# ETS_v8-nordic-split.net
KiCad netlist of a schematic drawn in Altium Designer
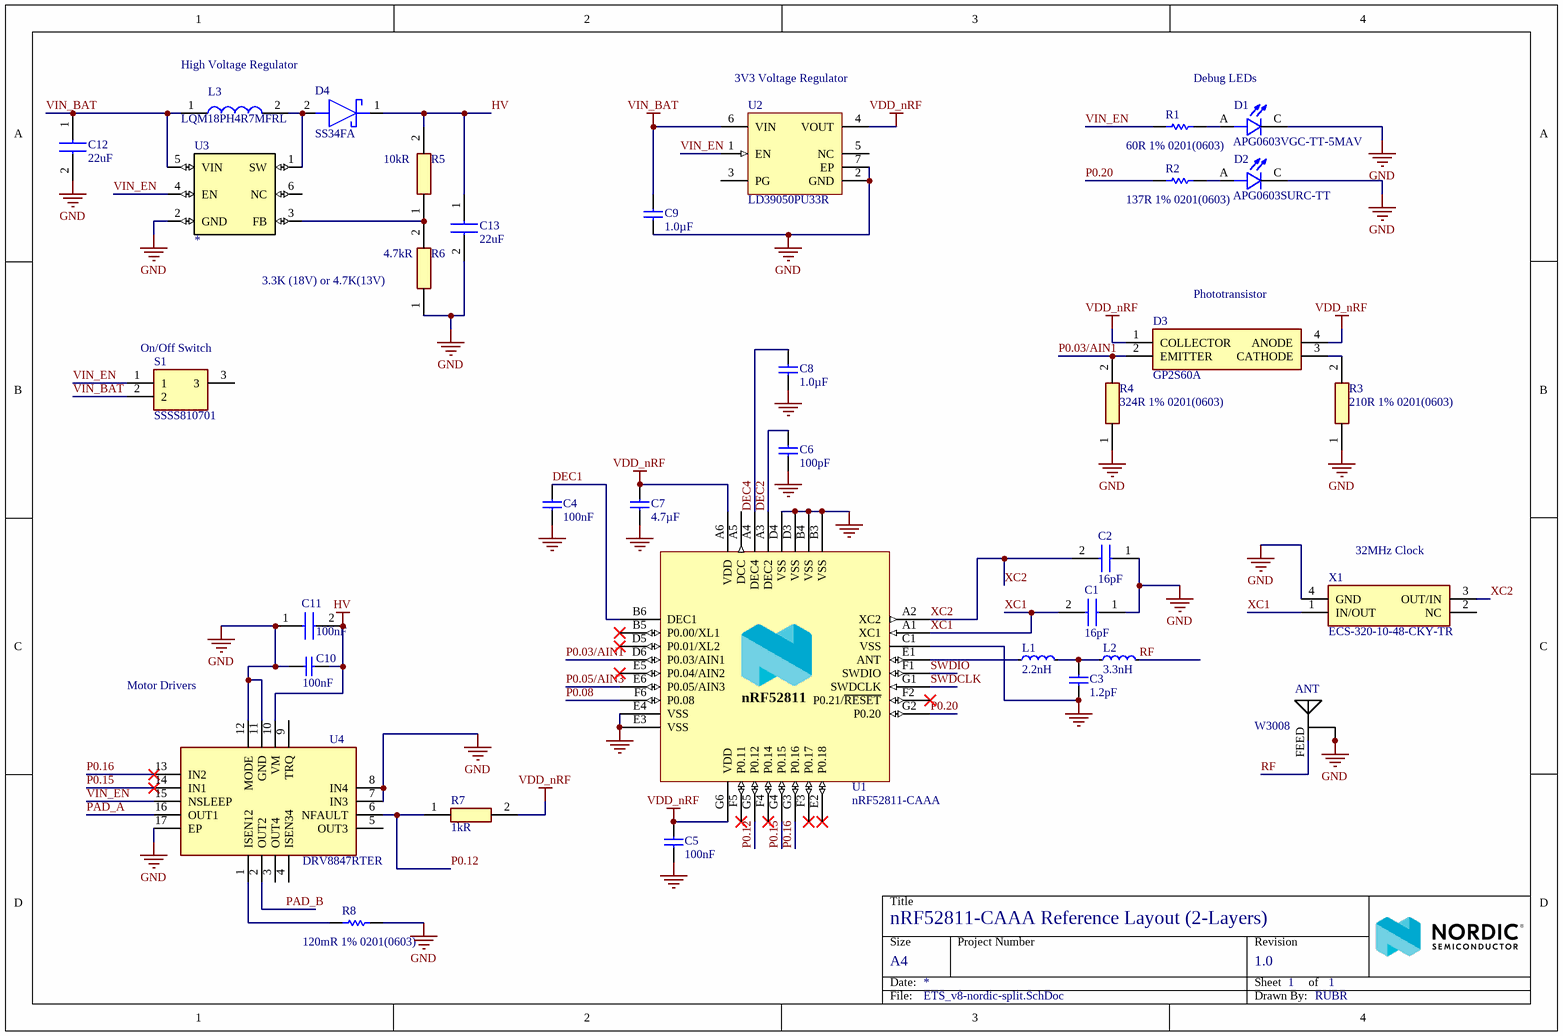
[diagram p0: ETS_v8-nordic-split.SchDoc]

(export (version "E")
  (design (tool "Eeschema 10.0.6"))
  (components
    (comp (ref "ANT")
      (value "W3008")
      (footprint "*ANTENNA_W3008W3008(Primary)")
      (description "2.4GHz Bluetooth Chip RF Antenna 2.4GHz ~ 2.483GHz 1.7dBi Solder Surface Mount")
      (fields (field (name "MF") "PulseLarsen Antennas"))
      (libsource (lib "W3008") (part "W3008"))
    )
    (comp (ref "C1")
      (value "16pF")
      (footprint "SamacSys:CAPC0603X33N")
      (description "Capacitor")
      (fields (field (name "MANUFACTURER_PART_NUMBER") "GRM0335C1H160JA01D"))
      (libsource (lib "*") (part "GRM0335C1H160JA01D"))
    )
    (comp (ref "C2")
      (value "16pF")
      (footprint "SamacSys:CAPC0603X33N")
      (description "Capacitor")
      (fields (field (name "MANUFACTURER_PART_NUMBER") "GRM0335C1H160JA01D"))
      (libsource (lib "*") (part "GRM0335C1H160JA01D"))
    )
    (comp (ref "C3")
      (value "1.2pF")
      (footprint "CAPC0603X03L_C")
      (description "Capacitor, NP0, ±5%")
      (fields (field (name "PART NUMBER") "C0201-1.2p") (field (name "PUBLISHER") "Nordic Semiconductor"))
      (libsource (lib "Nordic Passive DB") (part "CAP"))
    )
    (comp (ref "C4")
      (value "100nF")
      (footprint "CAPC0603X03L_C")
      (description "Capacitor, X5R, ±10%")
      (fields (field (name "PART NUMBER") "C0201-100n") (field (name "PUBLISHER") "Nordic Semiconductor"))
      (libsource (lib "Nordic Passive DB") (part "CAP"))
    )
    (comp (ref "C5")
      (value "100nF")
      (footprint "CAPC0603X03L_C")
      (description "Capacitor, X5R, ±10%")
      (fields (field (name "PART NUMBER") "C0201-100n") (field (name "PUBLISHER") "Nordic Semiconductor"))
      (libsource (lib "Nordic Passive DB") (part "CAP"))
    )
    (comp (ref "C6")
      (value "100pF")
      (footprint "CAPC0603X03L_C")
      (description "Capacitor, NP0, ±2%")
      (fields (field (name "PART NUMBER") "C0201-100p") (field (name "PUBLISHER") "Nordic Semiconductor"))
      (libsource (lib "Nordic Passive DB") (part "CAP"))
    )
    (comp (ref "C7")
      (value "4.7µF")
      (footprint "CAPC1608X06L")
      (description "Capacitor, X5R, ±10%")
      (fields (field (name "PART NUMBER") "C0603-4µ7") (field (name "PUBLISHER") "Nordic Semiconductor"))
      (libsource (lib "Nordic Passive DB") (part "CAP"))
    )
    (comp (ref "C8")
      (value "1.0µF")
      (footprint "CAPC1005X04L")
      (description "Capacitor, X5R, ±5%")
      (fields (field (name "PART NUMBER") "C0402-1µ0") (field (name "PUBLISHER") "Nordic Semiconductor"))
      (libsource (lib "Nordic Passive DB") (part "CAP"))
    )
    (comp (ref "C9")
      (value "1.0µF")
      (footprint "CAPC1005X04L")
      (description "Capacitor, X5R, ±5%")
      (fields (field (name "PART NUMBER") "C0402-1µ0") (field (name "PUBLISHER") "Nordic Semiconductor"))
      (libsource (lib "Nordic Passive DB") (part "CAP"))
    )
    (comp (ref "C10")
      (value "100nF")
      (footprint "CAPC0603X03L_C")
      (description "Capacitor, X5R, ±10%")
      (fields (field (name "PART NUMBER") "C0201-100n") (field (name "PUBLISHER") "Nordic Semiconductor"))
      (libsource (lib "exoNail_v1") (part "C0201-100n"))
    )
    (comp (ref "C11")
      (value "100nF")
      (footprint "CAPC0603X03L_C")
      (description "Capacitor")
      (fields (field (name "MANUFACTURER_PART_NUMBER") "GRM188R61C106KAALD"))
      (libsource (lib "*") (part "GRM188R61C106KAALD"))
    )
    (comp (ref "C12")
      (value "22uF")
      (footprint "CAPC2012X145N")
      (description "Capacitor")
      (fields (field (name "MANUFACTURER_PART_NUMBER") "GRM21BR61E226ME44K"))
      (libsource (lib "MasterLib") (part "GRM21BR61E226ME44K"))
    )
    (comp (ref "C13")
      (value "22uF")
      (footprint "CAPC2012X145N")
      (description "Capacitor")
      (fields (field (name "MANUFACTURER_PART_NUMBER") "GRM21BR61E226ME44K"))
      (libsource (lib "MasterLib") (part "GRM21BR61E226ME44K"))
    )
    (comp (ref "D1")
      (value "APG0603VGC-TT-5MAV")
      (footprint "LED_APG0603SEC-E-TT")
      (description "Green 527nm LED Indication - Discrete 3V 2-SMD, 0201")
      (fields (field (name "MP") "APG0603SEC-E-TT") (field (name "MF") "Kingbright"))
      (libsource (lib "APG0603SEC-E-TT") (part "APG0603SEC-E-TT"))
    )
    (comp (ref "D2")
      (value "APG0603SURC-TT")
      (footprint "LED_APG0603SEC-E-TT")
      (description "Red 631nm LED Indication - Discrete 1.92V 2-SMD, 0201")
      (fields (field (name "MP") "APG0603SEC-E-TT") (field (name "MF") "Kingbright"))
      (libsource (lib "APG0603SEC-E-TT") (part "APG0603SEC-E-TT"))
    )
    (comp (ref "D3")
      (value "GP2S60A")
      (footprint "SamacSys:GP2S60B")
      (description "LED")
      (fields
        (field (name "MOUSER2 PART NUMBER") "852-GP2S60B")
        (field (name "MANUFACTURER_PART_NUMBER") "GP2S60B")
      )
      (libsource (lib "*") (part "GP2S60B"))
    )
    (comp (ref "D4")
      (value "SS34FA")
      (footprint "SamacSys:SODFL3618X143N")
      (description "Schottky Diode")
      (fields (field (name "MOUSER2 PART NUMBER") "512-SS34FA"))
      (libsource (lib "*") (part "SS34FA"))
    )
    (comp (ref "L1")
      (value "2.2nH")
      (footprint "INDC0603X03L_C")
      (description "High frequency chip inductor ±5%")
      (fields (field (name "PART NUMBER") "L0201-2n2") (field (name "PUBLISHER") "Nordic Semiconductor"))
      (libsource (lib "Nordic Passive DB") (part "IND"))
    )
    (comp (ref "L2")
      (value "3.3nH")
      (footprint "INDC0603X03L_C")
      (description "High frequency chip inductor ±5%")
      (fields (field (name "PART NUMBER") "L0201-3n3") (field (name "PUBLISHER") "Nordic Semiconductor"))
      (libsource (lib "Nordic Passive DB") (part "IND"))
    )
    (comp (ref "L3")
      (value "LQM18PH4R7MFRL")
      (footprint "SamacSys:LQW18CA32NJ00D")
      (description "Inductor")
      (fields (field (name "MOUSER2 PART NUMBER") "81-LQM18PH4R7MFRL"))
      (libsource (lib "*") (part "LQM18PH4R7MFRL"))
    )
    (comp (ref "R1")
      (value "60R 1% 0201(0603)")
      (footprint "RESC0201(0603)_L")
      (description "1R 0.05W 1% 0201 (0603 Metric)  SMD")
      (fields (field (name "POWER") "0.05 W") (field (name "TOLERANCE") "1 %"))
      (libsource (lib "Altium Content Vault") (part "RES"))
    )
    (comp (ref "R2")
      (value "137R 1% 0201(0603)")
      (footprint "RESC0201(0603)_L")
      (description "1R 0.05W 1% 0201 (0603 Metric)  SMD")
      (fields (field (name "POWER") "0.05 W") (field (name "TOLERANCE") "1 %"))
      (libsource (lib "Altium Content Vault") (part "RES"))
    )
    (comp (ref "R3")
      (value "210R 1% 0201(0603)")
      (footprint "SamacSys:RESC0603X26N")
      (description "Resistor")
      (fields
        (field (name "MOUSER2 PART NUMBER") "603-RC0201FR-0710KL")
        (field (name "MANUFACTURER_PART_NUMBER") "RC0201FR-0710KL")
      )
      (libsource (lib "*") (part "RC0201FR-0710KL"))
    )
    (comp (ref "R4")
      (value "324R 1% 0201(0603)")
      (footprint "SamacSys:RESC0603X26N")
      (description "Resistor")
      (fields (field (name "MANUFACTURER_PART_NUMBER") "RC0201FR-07390RL"))
      (libsource (lib "*") (part "RC0201FR-07390RL"))
    )
    (comp (ref "R5")
      (value "10kR")
      (footprint "SamacSys:RESC0603X26N")
      (description "Resistor")
      (fields (field (name "MANUFACTURER_PART_NUMBER") "RC0201FR-07100KL"))
      (libsource (lib "*") (part "RC0201FR-07100KL"))
    )
    (comp (ref "R6")
      (value "4.7kR")
      (footprint "SamacSys:RESC0603X28N")
      (description "Resistor")
      (fields (field (name "MANUFACTURER_PART_NUMBER") "CRCW02014K70FKED"))
      (libsource (lib "*") (part "CRCW02014K70FKED"))
    )
    (comp (ref "R7")
      (value "1kR")
      (footprint "SamacSys:RESC0603X28N")
      (description "Resistor")
      (fields (field (name "MANUFACTURER_PART_NUMBER") "CRCW02011K00FNED"))
      (libsource (lib "*") (part "CRCW02011K00FNED"))
    )
    (comp (ref "R8")
      (value "120mR 1% 0201(0603)")
      (footprint "RESC0201(0603)_L")
      (description "1R 0.05W 1% 0201 (0603 Metric)  SMD")
      (fields (field (name "POWER") "0.05 W") (field (name "TOLERANCE") "1 %"))
      (libsource (lib "Altium Content Vault") (part "RES"))
    )
    (comp (ref "S1")
      (value "SSSS810701")
      (footprint "SamacSys:SSSS810701")
      (description "Switch")
      (fields (field (name "MOUSER2 PART NUMBER") "688-SSSS810701"))
      (libsource (lib "*") (part "SSSS810701"))
    )
    (comp (ref "U1")
      (value "nRF52811-CAAA")
      (footprint "BGA33C40P6X6_247X246X50")
      (description "Multi-protocol Bluetooth Low Energy, IEEE 802.15.4, ANT and 2.4GHz proprietary system-on-chip")
      (fields
        (field (name "PART NUMBER") "nRF52811-CAAAA0")
        (field (name "MANUFACTURER") "Nordic Semiconductor")
        (field (name "PUBLISHER") "Nordic Semiconductor")
      )
      (libsource (lib "Nordic Active DB") (part "nRF52811_CAAA"))
    )
    (comp (ref "U2")
      (value "LD39050PU33R")
      (footprint "DFN6D_L")
      (description "500 mA Low Quiescent Current Low Noise Voltage Regulator, 3.3V, 6-Pin VDFDPN, Tape and Reel")
      (libsource (lib "Altium Content Vault") (part "PM-REG-LD39050-SQ7"))
    )
    (comp (ref "U3")
      (value "*")
      (footprint "*SOT23-6")
      (description "High Efficiency 1.2MHz\r\n2A Step Up Converter")
      (libsource (lib "MasterLib") (part "MT3608"))
    )
    (comp (ref "U4")
      (value "DRV8847RTER")
      (footprint "SamacSys:QFN50P300X300X80-17N-D")
      (description "Integrated Circuit")
      (fields (field (name "MOUSER2 PART NUMBER") "595-DRV8847RTER"))
      (libsource (lib "*") (part "DRV8847RTER"))
    )
    (comp (ref "X1")
      (value "ECS-320-10-48-CKY-TR")
      (footprint "SamacSys:ECS240848CKYTR")
      (description "Crystal or Oscillator")
      (libsource (lib "*") (part "ECS-320-10-48-CKY-TR"))
    )
  )
  (nets
    (net (code "1") (name "/DEC1") (class "Default")
      (node (ref "C4") (pin "1") (pinfunction "1_1") (pintype "passive"))
      (node (ref "U1") (pin "B6") (pinfunction "DEC1_B6") (pintype "power_in"))
    )
    (net (code "2") (name "/DEC2") (class "Default")
      (node (ref "C6") (pin "2") (pinfunction "2_2") (pintype "passive"))
      (node (ref "U1") (pin "A3") (pinfunction "DEC2_A3") (pintype "power_in"))
    )
    (net (code "3") (name "/DEC4") (class "Default")
      (node (ref "C8") (pin "2") (pinfunction "2_2") (pintype "passive"))
      (node (ref "U1") (pin "A4") (pinfunction "DEC4_A4") (pintype "power_in"))
    )
    (net (code "4") (name "/P0.03{slash}AIN1") (class "Default")
      (node (ref "D3") (pin "2") (pinfunction "EMITTER_2") (pintype "passive"))
      (node (ref "R4") (pin "2") (pinfunction "2_2") (pintype "passive"))
      (node (ref "U1") (pin "D6") (pinfunction "P0.03/AIN1_D6") (pintype "bidirectional"))
    )
    (net (code "5") (name "/P0.05{slash}AIN3") (class "Default")
      (node (ref "U1") (pin "E6") (pinfunction "P0.05/AIN3_E6") (pintype "bidirectional"))
    )
    (net (code "6") (name "/P0.08") (class "Default")
      (node (ref "U1") (pin "F6") (pinfunction "P0.08_F6") (pintype "bidirectional"))
    )
    (net (code "7") (name "/P0.12") (class "Default")
      (node (ref "R7") (pin "1") (pinfunction "1_1") (pintype "passive"))
      (node (ref "U1") (pin "G5") (pinfunction "P0.12_G5") (pintype "bidirectional"))
      (node (ref "U4") (pin "6") (pinfunction "NFAULT_6") (pintype "passive"))
    )
    (net (code "8") (name "/P0.15") (class "Default")
      (node (ref "U1") (pin "G4") (pinfunction "P0.15_G4") (pintype "bidirectional"))
      (node (ref "U4") (pin "14") (pinfunction "IN1_14") (pintype "passive"))
    )
    (net (code "9") (name "/P0.16") (class "Default")
      (node (ref "U1") (pin "G3") (pinfunction "P0.16_G3") (pintype "bidirectional"))
      (node (ref "U4") (pin "13") (pinfunction "IN2_13") (pintype "passive"))
    )
    (net (code "10") (name "/P0.20") (class "Default")
      (node (ref "R2") (pin "1") (pinfunction "1_1") (pintype "passive"))
      (node (ref "U1") (pin "G2") (pinfunction "P0.20_G2") (pintype "bidirectional"))
    )
    (net (code "11") (name "/PAD_A") (class "Default")
      (node (ref "U4") (pin "16") (pinfunction "OUT1_16") (pintype "passive"))
    )
    (net (code "12") (name "/PAD_B") (class "Default")
      (node (ref "U4") (pin "2") (pinfunction "OUT2_2") (pintype "passive"))
    )
    (net (code "13") (name "/RF") (class "Default")
      (node (ref "ANT") (pin "FEED") (pinfunction "FEED_FEED") (pintype "passive"))
      (node (ref "L2") (pin "2") (pinfunction "2_2") (pintype "passive"))
    )
    (net (code "14") (name "/SWDCLK") (class "Default")
      (node (ref "U1") (pin "G1") (pinfunction "SWDCLK_G1") (pintype "input"))
    )
    (net (code "15") (name "/SWDIO") (class "Default")
      (node (ref "U1") (pin "F1") (pinfunction "SWDIO_F1") (pintype "bidirectional"))
    )
    (net (code "16") (name "/VIN_EN") (class "Default")
      (node (ref "R1") (pin "1") (pinfunction "1_1") (pintype "passive"))
      (node (ref "S1") (pin "1") (pinfunction "1_1") (pintype "passive"))
      (node (ref "U2") (pin "1") (pinfunction "EN_1") (pintype "input"))
      (node (ref "U3") (pin "4") (pinfunction "EN_4") (pintype "bidirectional"))
      (node (ref "U4") (pin "15") (pinfunction "NSLEEP_15") (pintype "passive"))
    )
    (net (code "17") (name "/XC1") (class "Default")
      (node (ref "C1") (pin "2") (pinfunction "2_2") (pintype "passive"))
      (node (ref "U1") (pin "A1") (pinfunction "XC1_A1") (pintype "input"))
      (node (ref "X1") (pin "1") (pinfunction "IN/OUT_1") (pintype "passive"))
    )
    (net (code "18") (name "/XC2") (class "Default")
      (node (ref "C2") (pin "2") (pinfunction "2_2") (pintype "passive"))
      (node (ref "U1") (pin "A2") (pinfunction "XC2_A2") (pintype "output"))
      (node (ref "X1") (pin "3") (pinfunction "OUT/IN_3") (pintype "passive"))
    )
    (net (code "19") (name "GND") (class "Default")
      (node (ref "ANT") (pin "G1") (pinfunction "GND_G1") (pintype "passive"))
      (node (ref "ANT") (pin "G2") (pinfunction "GND_G2") (pintype "passive"))
      (node (ref "C1") (pin "1") (pinfunction "1_1") (pintype "passive"))
      (node (ref "C10") (pin "2") (pinfunction "2_2") (pintype "passive"))
      (node (ref "C11") (pin "1") (pinfunction "1_1") (pintype "passive"))
      (node (ref "C12") (pin "2") (pinfunction "2_2") (pintype "passive"))
      (node (ref "C13") (pin "2") (pinfunction "2_2") (pintype "passive"))
      (node (ref "C2") (pin "1") (pinfunction "1_1") (pintype "passive"))
      (node (ref "C3") (pin "1") (pinfunction "1_1") (pintype "passive"))
      (node (ref "C4") (pin "2") (pinfunction "2_2") (pintype "passive"))
      (node (ref "C5") (pin "2") (pinfunction "2_2") (pintype "passive"))
      (node (ref "C6") (pin "1") (pinfunction "1_1") (pintype "passive"))
      (node (ref "C7") (pin "2") (pinfunction "2_2") (pintype "passive"))
      (node (ref "C8") (pin "1") (pinfunction "1_1") (pintype "passive"))
      (node (ref "C9") (pin "1") (pinfunction "1_1") (pintype "passive"))
      (node (ref "D1") (pin "C") (pinfunction "C_C") (pintype "passive"))
      (node (ref "D2") (pin "C") (pinfunction "C_C") (pintype "passive"))
      (node (ref "R3") (pin "1") (pinfunction "1_1") (pintype "passive"))
      (node (ref "R4") (pin "1") (pinfunction "1_1") (pintype "passive"))
      (node (ref "R6") (pin "1") (pinfunction "1_1") (pintype "passive"))
      (node (ref "R8") (pin "2") (pinfunction "2_2") (pintype "passive"))
      (node (ref "U1") (pin "B3") (pinfunction "VSS_B3") (pintype "power_in"))
      (node (ref "U1") (pin "B4") (pinfunction "VSS_B4") (pintype "power_in"))
      (node (ref "U1") (pin "C1") (pinfunction "VSS_C1") (pintype "power_in"))
      (node (ref "U1") (pin "D3") (pinfunction "VSS_D3") (pintype "power_in"))
      (node (ref "U1") (pin "D4") (pinfunction "VSS_D4") (pintype "power_in"))
      (node (ref "U1") (pin "E3") (pinfunction "VSS_E3") (pintype "power_in"))
      (node (ref "U1") (pin "E4") (pinfunction "VSS_E4") (pintype "power_in"))
      (node (ref "U2") (pin "2") (pinfunction "GND_2") (pintype "power_in"))
      (node (ref "U2") (pin "7") (pinfunction "EP_7") (pintype "power_in"))
      (node (ref "U3") (pin "2") (pinfunction "GND_2") (pintype "bidirectional"))
      (node (ref "U4") (pin "11") (pinfunction "GND_11") (pintype "passive"))
      (node (ref "U4") (pin "12") (pinfunction "MODE_12") (pintype "passive"))
      (node (ref "U4") (pin "17") (pinfunction "EP_17") (pintype "passive"))
      (node (ref "U4") (pin "7") (pinfunction "IN3_7") (pintype "passive"))
      (node (ref "U4") (pin "8") (pinfunction "IN4_8") (pintype "passive"))
      (node (ref "X1") (pin "4") (pinfunction "GND_4") (pintype "passive"))
    )
    (net (code "20") (name "HV") (class "Default")
      (node (ref "C10") (pin "1") (pinfunction "1_1") (pintype "passive"))
      (node (ref "C11") (pin "2") (pinfunction "2_2") (pintype "passive"))
      (node (ref "C13") (pin "1") (pinfunction "1_1") (pintype "passive"))
      (node (ref "D4") (pin "1") (pinfunction "K_1") (pintype "passive"))
      (node (ref "R5") (pin "2") (pinfunction "2_2") (pintype "passive"))
      (node (ref "U4") (pin "10") (pinfunction "VM_10") (pintype "passive"))
    )
    (net (code "21") (name "Net-(C3-Pad2)") (class "Default")
      (node (ref "C3") (pin "2") (pinfunction "2_2") (pintype "passive"))
      (node (ref "L1") (pin "2") (pinfunction "2_2") (pintype "passive"))
      (node (ref "L2") (pin "1") (pinfunction "1_1") (pintype "passive"))
    )
    (net (code "22") (name "Net-(D1-PadA)") (class "Default")
      (node (ref "D1") (pin "A") (pinfunction "A_A") (pintype "passive"))
      (node (ref "R1") (pin "2") (pinfunction "2_2") (pintype "passive"))
    )
    (net (code "23") (name "Net-(D2-PadA)") (class "Default")
      (node (ref "D2") (pin "A") (pinfunction "A_A") (pintype "passive"))
      (node (ref "R2") (pin "2") (pinfunction "2_2") (pintype "passive"))
    )
    (net (code "24") (name "Net-(D3-CATHODE)") (class "Default")
      (node (ref "D3") (pin "3") (pinfunction "CATHODE_3") (pintype "passive"))
      (node (ref "R3") (pin "2") (pinfunction "2_2") (pintype "passive"))
    )
    (net (code "25") (name "Net-(D4-A)") (class "Default")
      (node (ref "D4") (pin "2") (pinfunction "A_2") (pintype "passive"))
      (node (ref "L3") (pin "2") (pinfunction "2_2") (pintype "passive"))
      (node (ref "U3") (pin "1") (pinfunction "SW_1") (pintype "bidirectional"))
    )
    (net (code "26") (name "Net-(U1-ANT)") (class "Default")
      (node (ref "L1") (pin "1") (pinfunction "1_1") (pintype "passive"))
      (node (ref "U1") (pin "E1") (pinfunction "ANT_E1") (pintype "bidirectional"))
    )
    (net (code "27") (name "Net-(U3-FB)") (class "Default")
      (node (ref "R5") (pin "1") (pinfunction "1_1") (pintype "passive"))
      (node (ref "R6") (pin "2") (pinfunction "2_2") (pintype "passive"))
      (node (ref "U3") (pin "3") (pinfunction "FB_3") (pintype "bidirectional"))
    )
    (net (code "28") (name "Net-(U4-ISEN12)") (class "Default")
      (node (ref "R8") (pin "1") (pinfunction "1_1") (pintype "passive"))
      (node (ref "U4") (pin "1") (pinfunction "ISEN12_1") (pintype "passive"))
    )
    (net (code "29") (name "VDD_nRF") (class "Default")
      (node (ref "C5") (pin "1") (pinfunction "1_1") (pintype "passive"))
      (node (ref "C7") (pin "1") (pinfunction "1_1") (pintype "passive"))
      (node (ref "D3") (pin "1") (pinfunction "COLLECTOR_1") (pintype "passive"))
      (node (ref "D3") (pin "4") (pinfunction "ANODE_4") (pintype "passive"))
      (node (ref "R7") (pin "2") (pinfunction "2_2") (pintype "passive"))
      (node (ref "U1") (pin "A6") (pinfunction "VDD_A6") (pintype "power_in"))
      (node (ref "U1") (pin "G6") (pinfunction "VDD_G6") (pintype "power_in"))
      (node (ref "U2") (pin "4") (pinfunction "VOUT_4") (pintype "power_in"))
    )
    (net (code "30") (name "VIN_BAT") (class "Default")
      (node (ref "C12") (pin "1") (pinfunction "1_1") (pintype "passive"))
      (node (ref "C9") (pin "2") (pinfunction "2_2") (pintype "passive"))
      (node (ref "L3") (pin "1") (pinfunction "1_1") (pintype "passive"))
      (node (ref "S1") (pin "2") (pinfunction "2_2") (pintype "passive"))
      (node (ref "U2") (pin "6") (pinfunction "VIN_6") (pintype "power_in"))
      (node (ref "U3") (pin "5") (pinfunction "VIN_5") (pintype "bidirectional"))
    )
    (net (code "31") (name "unconnected-(S1-Pad3)") (class "Default")
      (node (ref "S1") (pin "3") (pinfunction "3_3") (pintype "passive"))
    )
    (net (code "32") (name "unconnected-(U1-DCC-PadA5)") (class "Default")
      (node (ref "U1") (pin "A5") (pinfunction "DCC_A5") (pintype "output"))
    )
    (net (code "33") (name "unconnected-(U1-P0.00{slash}XL1-PadB5)") (class "Default")
      (node (ref "U1") (pin "B5") (pinfunction "P0.00/XL1_B5") (pintype "bidirectional+no_connect"))
    )
    (net (code "34") (name "unconnected-(U1-P0.01{slash}XL2-PadD5)") (class "Default")
      (node (ref "U1") (pin "D5") (pinfunction "P0.01/XL2_D5") (pintype "bidirectional+no_connect"))
    )
    (net (code "35") (name "unconnected-(U1-P0.04{slash}AIN2-PadE5)") (class "Default")
      (node (ref "U1") (pin "E5") (pinfunction "P0.04/AIN2_E5") (pintype "bidirectional+no_connect"))
    )
    (net (code "36") (name "unconnected-(U1-P0.11-PadF5)") (class "Default")
      (node (ref "U1") (pin "F5") (pinfunction "P0.11_F5") (pintype "bidirectional+no_connect"))
    )
    (net (code "37") (name "unconnected-(U1-P0.14-PadF4)") (class "Default")
      (node (ref "U1") (pin "F4") (pinfunction "P0.14_F4") (pintype "bidirectional+no_connect"))
    )
    (net (code "38") (name "unconnected-(U1-P0.17-PadF3)") (class "Default")
      (node (ref "U1") (pin "F3") (pinfunction "P0.17_F3") (pintype "bidirectional+no_connect"))
    )
    (net (code "39") (name "unconnected-(U1-P0.18-PadE2)") (class "Default")
      (node (ref "U1") (pin "E2") (pinfunction "P0.18_E2") (pintype "bidirectional+no_connect"))
    )
    (net (code "40") (name "unconnected-(U1-P0.21{slash}~{RESET}-PadF2)") (class "Default")
      (node (ref "U1") (pin "F2") (pinfunction "P0.21/~{RESET}_F2") (pintype "bidirectional+no_connect"))
    )
    (net (code "41") (name "unconnected-(U2-NC-Pad5)") (class "Default")
      (node (ref "U2") (pin "5") (pinfunction "NC_5") (pintype "passive"))
    )
    (net (code "42") (name "unconnected-(U2-PG-Pad3)") (class "Default")
      (node (ref "U2") (pin "3") (pinfunction "PG_3") (pintype "open_collector"))
    )
    (net (code "43") (name "unconnected-(U3-NC-Pad6)") (class "Default")
      (node (ref "U3") (pin "6") (pinfunction "NC_6") (pintype "bidirectional"))
    )
    (net (code "44") (name "unconnected-(U4-ISEN34-Pad4)") (class "Default")
      (node (ref "U4") (pin "4") (pinfunction "ISEN34_4") (pintype "passive"))
    )
    (net (code "45") (name "unconnected-(U4-OUT3-Pad5)") (class "Default")
      (node (ref "U4") (pin "5") (pinfunction "OUT3_5") (pintype "passive"))
    )
    (net (code "46") (name "unconnected-(U4-OUT4-Pad3)") (class "Default")
      (node (ref "U4") (pin "3") (pinfunction "OUT4_3") (pintype "passive"))
    )
    (net (code "47") (name "unconnected-(U4-TRQ-Pad9)") (class "Default")
      (node (ref "U4") (pin "9") (pinfunction "TRQ_9") (pintype "passive"))
    )
    (net (code "48") (name "unconnected-(X1-NC-Pad2)") (class "Default")
      (node (ref "X1") (pin "2") (pinfunction "NC_2") (pintype "passive"))
    )
  )
)
